# 4x4-soundboard_TH.net
KiCad netlist of a schematic drawn in EAGLE
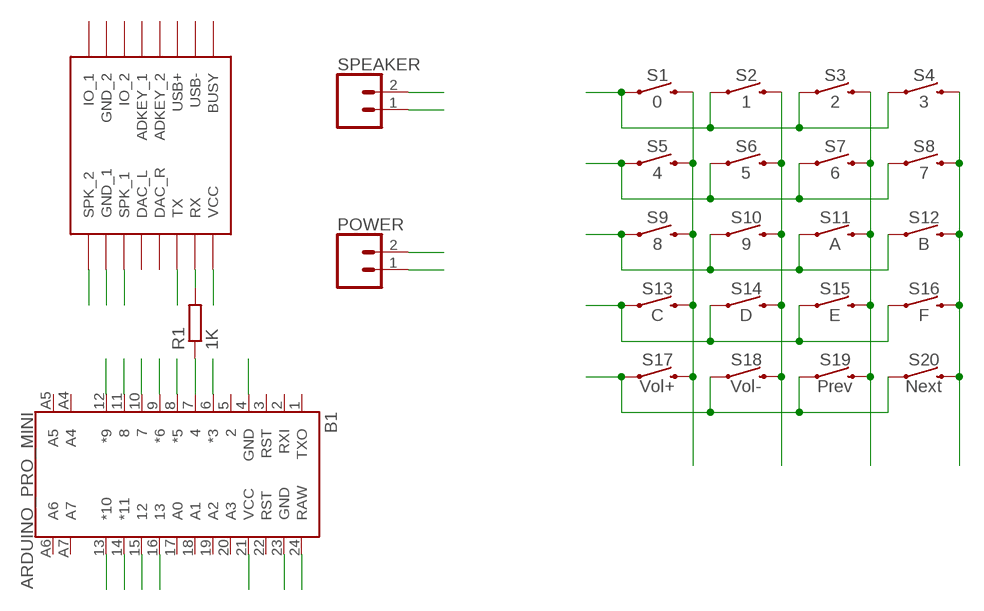
[diagram p0: schematic, sheet 1]

(export (version "E")
  (design (tool "Eeschema 10.0.6"))
  (components
    (comp (ref "B1")
      (value "ARDUINO_PRO_MINI")
      (footprint "eagle-import:ARDUINO_PRO_MINI")
      (libsource (lib "eagle-import") (part "ARDUINO_PRO_MINI"))
    )
    (comp (ref "POWER")
      (value "CONN_02")
      (footprint "eagle-import:1X02")
      (libsource (lib "eagle-import") (part "CONN_02"))
    )
    (comp (ref "R1")
      (value "1K")
      (footprint "eagle-import:0207_10")
      (libsource (lib "eagle-import") (part "R-EU_0207/10"))
    )
    (comp (ref "S1")
      (value "0")
      (footprint "eagle-import:TACTILE_SWITCH_PTH_6.0MM")
      (libsource (lib "eagle-import") (part "MOMENTARY-SWITCH-SPST-PTH-6.0MM"))
    )
    (comp (ref "S2")
      (value "1")
      (footprint "eagle-import:TACTILE_SWITCH_PTH_6.0MM")
      (libsource (lib "eagle-import") (part "MOMENTARY-SWITCH-SPST-PTH-6.0MM"))
    )
    (comp (ref "S3")
      (value "2")
      (footprint "eagle-import:TACTILE_SWITCH_PTH_6.0MM")
      (libsource (lib "eagle-import") (part "MOMENTARY-SWITCH-SPST-PTH-6.0MM"))
    )
    (comp (ref "S4")
      (value "3")
      (footprint "eagle-import:TACTILE_SWITCH_PTH_6.0MM")
      (libsource (lib "eagle-import") (part "MOMENTARY-SWITCH-SPST-PTH-6.0MM"))
    )
    (comp (ref "S5")
      (value "4")
      (footprint "eagle-import:TACTILE_SWITCH_PTH_6.0MM")
      (libsource (lib "eagle-import") (part "MOMENTARY-SWITCH-SPST-PTH-6.0MM"))
    )
    (comp (ref "S6")
      (value "5")
      (footprint "eagle-import:TACTILE_SWITCH_PTH_6.0MM")
      (libsource (lib "eagle-import") (part "MOMENTARY-SWITCH-SPST-PTH-6.0MM"))
    )
    (comp (ref "S7")
      (value "6")
      (footprint "eagle-import:TACTILE_SWITCH_PTH_6.0MM")
      (libsource (lib "eagle-import") (part "MOMENTARY-SWITCH-SPST-PTH-6.0MM"))
    )
    (comp (ref "S8")
      (value "7")
      (footprint "eagle-import:TACTILE_SWITCH_PTH_6.0MM")
      (libsource (lib "eagle-import") (part "MOMENTARY-SWITCH-SPST-PTH-6.0MM"))
    )
    (comp (ref "S9")
      (value "8")
      (footprint "eagle-import:TACTILE_SWITCH_PTH_6.0MM")
      (libsource (lib "eagle-import") (part "MOMENTARY-SWITCH-SPST-PTH-6.0MM"))
    )
    (comp (ref "S10")
      (value "9")
      (footprint "eagle-import:TACTILE_SWITCH_PTH_6.0MM")
      (libsource (lib "eagle-import") (part "MOMENTARY-SWITCH-SPST-PTH-6.0MM"))
    )
    (comp (ref "S11")
      (value "A")
      (footprint "eagle-import:TACTILE_SWITCH_PTH_6.0MM")
      (libsource (lib "eagle-import") (part "MOMENTARY-SWITCH-SPST-PTH-6.0MM"))
    )
    (comp (ref "S12")
      (value "B")
      (footprint "eagle-import:TACTILE_SWITCH_PTH_6.0MM")
      (libsource (lib "eagle-import") (part "MOMENTARY-SWITCH-SPST-PTH-6.0MM"))
    )
    (comp (ref "S13")
      (value "C")
      (footprint "eagle-import:TACTILE_SWITCH_PTH_6.0MM")
      (libsource (lib "eagle-import") (part "MOMENTARY-SWITCH-SPST-PTH-6.0MM"))
    )
    (comp (ref "S14")
      (value "D")
      (footprint "eagle-import:TACTILE_SWITCH_PTH_6.0MM")
      (libsource (lib "eagle-import") (part "MOMENTARY-SWITCH-SPST-PTH-6.0MM"))
    )
    (comp (ref "S15")
      (value "E")
      (footprint "eagle-import:TACTILE_SWITCH_PTH_6.0MM")
      (libsource (lib "eagle-import") (part "MOMENTARY-SWITCH-SPST-PTH-6.0MM"))
    )
    (comp (ref "S16")
      (value "F")
      (footprint "eagle-import:TACTILE_SWITCH_PTH_6.0MM")
      (libsource (lib "eagle-import") (part "MOMENTARY-SWITCH-SPST-PTH-6.0MM"))
    )
    (comp (ref "S17")
      (value "Vol+")
      (footprint "eagle-import:TACTILE_SWITCH_PTH_6.0MM")
      (libsource (lib "eagle-import") (part "MOMENTARY-SWITCH-SPST-PTH-6.0MM"))
    )
    (comp (ref "S18")
      (value "Vol-")
      (footprint "eagle-import:TACTILE_SWITCH_PTH_6.0MM")
      (libsource (lib "eagle-import") (part "MOMENTARY-SWITCH-SPST-PTH-6.0MM"))
    )
    (comp (ref "S19")
      (value "Prev")
      (footprint "eagle-import:TACTILE_SWITCH_PTH_6.0MM")
      (libsource (lib "eagle-import") (part "MOMENTARY-SWITCH-SPST-PTH-6.0MM"))
    )
    (comp (ref "S20")
      (value "Next")
      (footprint "eagle-import:TACTILE_SWITCH_PTH_6.0MM")
      (libsource (lib "eagle-import") (part "MOMENTARY-SWITCH-SPST-PTH-6.0MM"))
    )
    (comp (ref "SPEAKER")
      (value "CONN_02")
      (footprint "eagle-import:1X02")
      (libsource (lib "eagle-import") (part "CONN_02"))
    )
    (comp (ref "U$1")
      (value "DFPLAYER")
      (footprint "eagle-import:DFPLAYER")
      (libsource (lib "eagle-import") (part "DFPLAYER"))
    )
  )
  (nets
    (net (code "1") (name "/5V") (class "Default")
      (node (ref "B1") (pin "21") (pinfunction "VCC_21") (pintype "power_in"))
      (node (ref "U$1") (pin "VCC") (pinfunction "VCC_VCC") (pintype "bidirectional"))
    )
    (net (code "2") (name "/COL1") (class "Default")
      (node (ref "B1") (pin "13") (pinfunction "*10_13") (pintype "bidirectional"))
      (node (ref "S1") (pin "3") (pinfunction "2_3") (pintype "passive"))
      (node (ref "S13") (pin "3") (pinfunction "2_3") (pintype "passive"))
      (node (ref "S17") (pin "3") (pinfunction "2_3") (pintype "passive"))
      (node (ref "S5") (pin "3") (pinfunction "2_3") (pintype "passive"))
      (node (ref "S9") (pin "3") (pinfunction "2_3") (pintype "passive"))
    )
    (net (code "3") (name "/COL2") (class "Default")
      (node (ref "B1") (pin "14") (pinfunction "*11_14") (pintype "bidirectional"))
      (node (ref "S10") (pin "3") (pinfunction "2_3") (pintype "passive"))
      (node (ref "S14") (pin "3") (pinfunction "2_3") (pintype "passive"))
      (node (ref "S18") (pin "3") (pinfunction "2_3") (pintype "passive"))
      (node (ref "S2") (pin "3") (pinfunction "2_3") (pintype "passive"))
      (node (ref "S6") (pin "3") (pinfunction "2_3") (pintype "passive"))
    )
    (net (code "4") (name "/COL3") (class "Default")
      (node (ref "B1") (pin "15") (pinfunction "12_15") (pintype "bidirectional"))
      (node (ref "S11") (pin "3") (pinfunction "2_3") (pintype "passive"))
      (node (ref "S15") (pin "3") (pinfunction "2_3") (pintype "passive"))
      (node (ref "S19") (pin "3") (pinfunction "2_3") (pintype "passive"))
      (node (ref "S3") (pin "3") (pinfunction "2_3") (pintype "passive"))
      (node (ref "S7") (pin "3") (pinfunction "2_3") (pintype "passive"))
    )
    (net (code "5") (name "/COL4") (class "Default")
      (node (ref "B1") (pin "16") (pinfunction "13_16") (pintype "bidirectional"))
      (node (ref "S12") (pin "3") (pinfunction "2_3") (pintype "passive"))
      (node (ref "S16") (pin "3") (pinfunction "2_3") (pintype "passive"))
      (node (ref "S20") (pin "3") (pinfunction "2_3") (pintype "passive"))
      (node (ref "S4") (pin "3") (pinfunction "2_3") (pintype "passive"))
      (node (ref "S8") (pin "3") (pinfunction "2_3") (pintype "passive"))
    )
    (net (code "6") (name "/GND") (class "Default")
      (node (ref "B1") (pin "23") (pinfunction "GND_23") (pintype "power_in"))
      (node (ref "B1") (pin "4") (pinfunction "GND_4") (pintype "power_in"))
      (node (ref "POWER") (pin "2") (pinfunction "2_2") (pintype "passive"))
      (node (ref "U$1") (pin "GND_1") (pinfunction "GND_1_GND_1") (pintype "bidirectional"))
    )
    (net (code "7") (name "/ROW1") (class "Default")
      (node (ref "B1") (pin "8") (pinfunction "*5_8") (pintype "bidirectional"))
      (node (ref "S1") (pin "1") (pinfunction "1_1") (pintype "passive"))
      (node (ref "S2") (pin "1") (pinfunction "1_1") (pintype "passive"))
      (node (ref "S3") (pin "1") (pinfunction "1_1") (pintype "passive"))
      (node (ref "S4") (pin "1") (pinfunction "1_1") (pintype "passive"))
    )
    (net (code "8") (name "/ROW2") (class "Default")
      (node (ref "B1") (pin "9") (pinfunction "*6_9") (pintype "bidirectional"))
      (node (ref "S5") (pin "1") (pinfunction "1_1") (pintype "passive"))
      (node (ref "S6") (pin "1") (pinfunction "1_1") (pintype "passive"))
      (node (ref "S7") (pin "1") (pinfunction "1_1") (pintype "passive"))
      (node (ref "S8") (pin "1") (pinfunction "1_1") (pintype "passive"))
    )
    (net (code "9") (name "/ROW3") (class "Default")
      (node (ref "B1") (pin "10") (pinfunction "7_10") (pintype "bidirectional"))
      (node (ref "S10") (pin "1") (pinfunction "1_1") (pintype "passive"))
      (node (ref "S11") (pin "1") (pinfunction "1_1") (pintype "passive"))
      (node (ref "S12") (pin "1") (pinfunction "1_1") (pintype "passive"))
      (node (ref "S9") (pin "1") (pinfunction "1_1") (pintype "passive"))
    )
    (net (code "10") (name "/ROW4") (class "Default")
      (node (ref "B1") (pin "11") (pinfunction "8_11") (pintype "bidirectional"))
      (node (ref "S13") (pin "1") (pinfunction "1_1") (pintype "passive"))
      (node (ref "S14") (pin "1") (pinfunction "1_1") (pintype "passive"))
      (node (ref "S15") (pin "1") (pinfunction "1_1") (pintype "passive"))
      (node (ref "S16") (pin "1") (pinfunction "1_1") (pintype "passive"))
    )
    (net (code "11") (name "/ROW5") (class "Default")
      (node (ref "B1") (pin "12") (pinfunction "*9_12") (pintype "bidirectional"))
      (node (ref "S17") (pin "1") (pinfunction "1_1") (pintype "passive"))
      (node (ref "S18") (pin "1") (pinfunction "1_1") (pintype "passive"))
      (node (ref "S19") (pin "1") (pinfunction "1_1") (pintype "passive"))
      (node (ref "S20") (pin "1") (pinfunction "1_1") (pintype "passive"))
    )
    (net (code "12") (name "/SPK+") (class "Default")
      (node (ref "SPEAKER") (pin "1") (pinfunction "1_1") (pintype "passive"))
      (node (ref "U$1") (pin "SPK1") (pinfunction "SPK_1_SPK1") (pintype "bidirectional"))
    )
    (net (code "13") (name "/SPK-") (class "Default")
      (node (ref "SPEAKER") (pin "2") (pinfunction "2_2") (pintype "passive"))
      (node (ref "U$1") (pin "SPK2") (pinfunction "SPK_2_SPK2") (pintype "bidirectional"))
    )
    (net (code "14") (name "/SRX") (class "Default")
      (node (ref "B1") (pin "6") (pinfunction "*3_6") (pintype "bidirectional"))
      (node (ref "U$1") (pin "TX") (pinfunction "TX_TX") (pintype "bidirectional"))
    )
    (net (code "15") (name "/VIN") (class "Default")
      (node (ref "B1") (pin "24") (pinfunction "RAW_24") (pintype "power_in"))
      (node (ref "POWER") (pin "1") (pinfunction "1_1") (pintype "passive"))
    )
    (net (code "16") (name "Net-(B1-4)") (class "Default")
      (node (ref "B1") (pin "7") (pinfunction "4_7") (pintype "bidirectional"))
      (node (ref "R1") (pin "1") (pinfunction "1_1") (pintype "passive"))
    )
    (net (code "17") (name "Net-(R1-Pad2)") (class "Default")
      (node (ref "R1") (pin "2") (pinfunction "2_2") (pintype "passive"))
      (node (ref "U$1") (pin "RX") (pinfunction "RX_RX") (pintype "bidirectional"))
    )
    (net (code "18") (name "unconnected-(B1-2-Pad5)") (class "Default")
      (node (ref "B1") (pin "5") (pinfunction "2_5") (pintype "bidirectional"))
    )
    (net (code "19") (name "unconnected-(B1-A0-Pad17)") (class "Default")
      (node (ref "B1") (pin "17") (pinfunction "A0_17") (pintype "bidirectional"))
    )
    (net (code "20") (name "unconnected-(B1-A1-Pad18)") (class "Default")
      (node (ref "B1") (pin "18") (pinfunction "A1_18") (pintype "bidirectional"))
    )
    (net (code "21") (name "unconnected-(B1-A2-Pad19)") (class "Default")
      (node (ref "B1") (pin "19") (pinfunction "A2_19") (pintype "bidirectional"))
    )
    (net (code "22") (name "unconnected-(B1-A3-Pad20)") (class "Default")
      (node (ref "B1") (pin "20") (pinfunction "A3_20") (pintype "bidirectional"))
    )
    (net (code "23") (name "unconnected-(B1-PadA4)") (class "Default")
      (node (ref "B1") (pin "A4") (pinfunction "A4_A4") (pintype "bidirectional"))
    )
    (net (code "24") (name "unconnected-(B1-PadA5)") (class "Default")
      (node (ref "B1") (pin "A5") (pinfunction "A5_A5") (pintype "bidirectional"))
    )
    (net (code "25") (name "unconnected-(B1-PadA6)") (class "Default")
      (node (ref "B1") (pin "A6") (pinfunction "A6_A6") (pintype "bidirectional"))
    )
    (net (code "26") (name "unconnected-(B1-PadA7)") (class "Default")
      (node (ref "B1") (pin "A7") (pinfunction "A7_A7") (pintype "bidirectional"))
    )
    (net (code "27") (name "unconnected-(B1-RST-Pad3)") (class "Default")
      (node (ref "B1") (pin "3") (pinfunction "RST_3") (pintype "bidirectional"))
    )
    (net (code "28") (name "unconnected-(B1-RST-Pad22)") (class "Default")
      (node (ref "B1") (pin "22") (pinfunction "RST_22") (pintype "bidirectional"))
    )
    (net (code "29") (name "unconnected-(B1-RXI-Pad2)") (class "Default")
      (node (ref "B1") (pin "2") (pinfunction "RXI_2") (pintype "bidirectional"))
    )
    (net (code "30") (name "unconnected-(B1-TXO-Pad1)") (class "Default")
      (node (ref "B1") (pin "1") (pinfunction "TXO_1") (pintype "bidirectional"))
    )
    (net (code "31") (name "unconnected-(U$1-ADKEY_1-PadADKEY1)") (class "Default")
      (node (ref "U$1") (pin "ADKEY1") (pinfunction "ADKEY_1_ADKEY1") (pintype "bidirectional"))
    )
    (net (code "32") (name "unconnected-(U$1-ADKEY_2-PadADKEY2)") (class "Default")
      (node (ref "U$1") (pin "ADKEY2") (pinfunction "ADKEY_2_ADKEY2") (pintype "bidirectional"))
    )
    (net (code "33") (name "unconnected-(U$1-IO_1-PadIO1)") (class "Default")
      (node (ref "U$1") (pin "IO1") (pinfunction "IO_1_IO1") (pintype "bidirectional"))
    )
    (net (code "34") (name "unconnected-(U$1-IO_2-PadIO2)") (class "Default")
      (node (ref "U$1") (pin "IO2") (pinfunction "IO_2_IO2") (pintype "bidirectional"))
    )
    (net (code "35") (name "unconnected-(U$1-PadBUSY)") (class "Default")
      (node (ref "U$1") (pin "BUSY") (pinfunction "BUSY_BUSY") (pintype "bidirectional"))
    )
    (net (code "36") (name "unconnected-(U$1-PadDAC_L)") (class "Default")
      (node (ref "U$1") (pin "DAC_L") (pinfunction "DAC_L_DAC_L") (pintype "bidirectional"))
    )
    (net (code "37") (name "unconnected-(U$1-PadDAC_R)") (class "Default")
      (node (ref "U$1") (pin "DAC_R") (pinfunction "DAC_R_DAC_R") (pintype "bidirectional"))
    )
    (net (code "38") (name "unconnected-(U$1-PadGND_2)") (class "Default")
      (node (ref "U$1") (pin "GND_2") (pinfunction "GND_2_GND_2") (pintype "bidirectional"))
    )
    (net (code "39") (name "unconnected-(U$1-PadUSB+)") (class "Default")
      (node (ref "U$1") (pin "USB+") (pinfunction "USB+_USB+") (pintype "bidirectional"))
    )
    (net (code "40") (name "unconnected-(U$1-PadUSB-)") (class "Default")
      (node (ref "U$1") (pin "USB-") (pinfunction "USB-_USB-") (pintype "bidirectional"))
    )
  )
)
